# Pulgarcito_2.net
KiCad netlist of a schematic drawn in EasyEDA
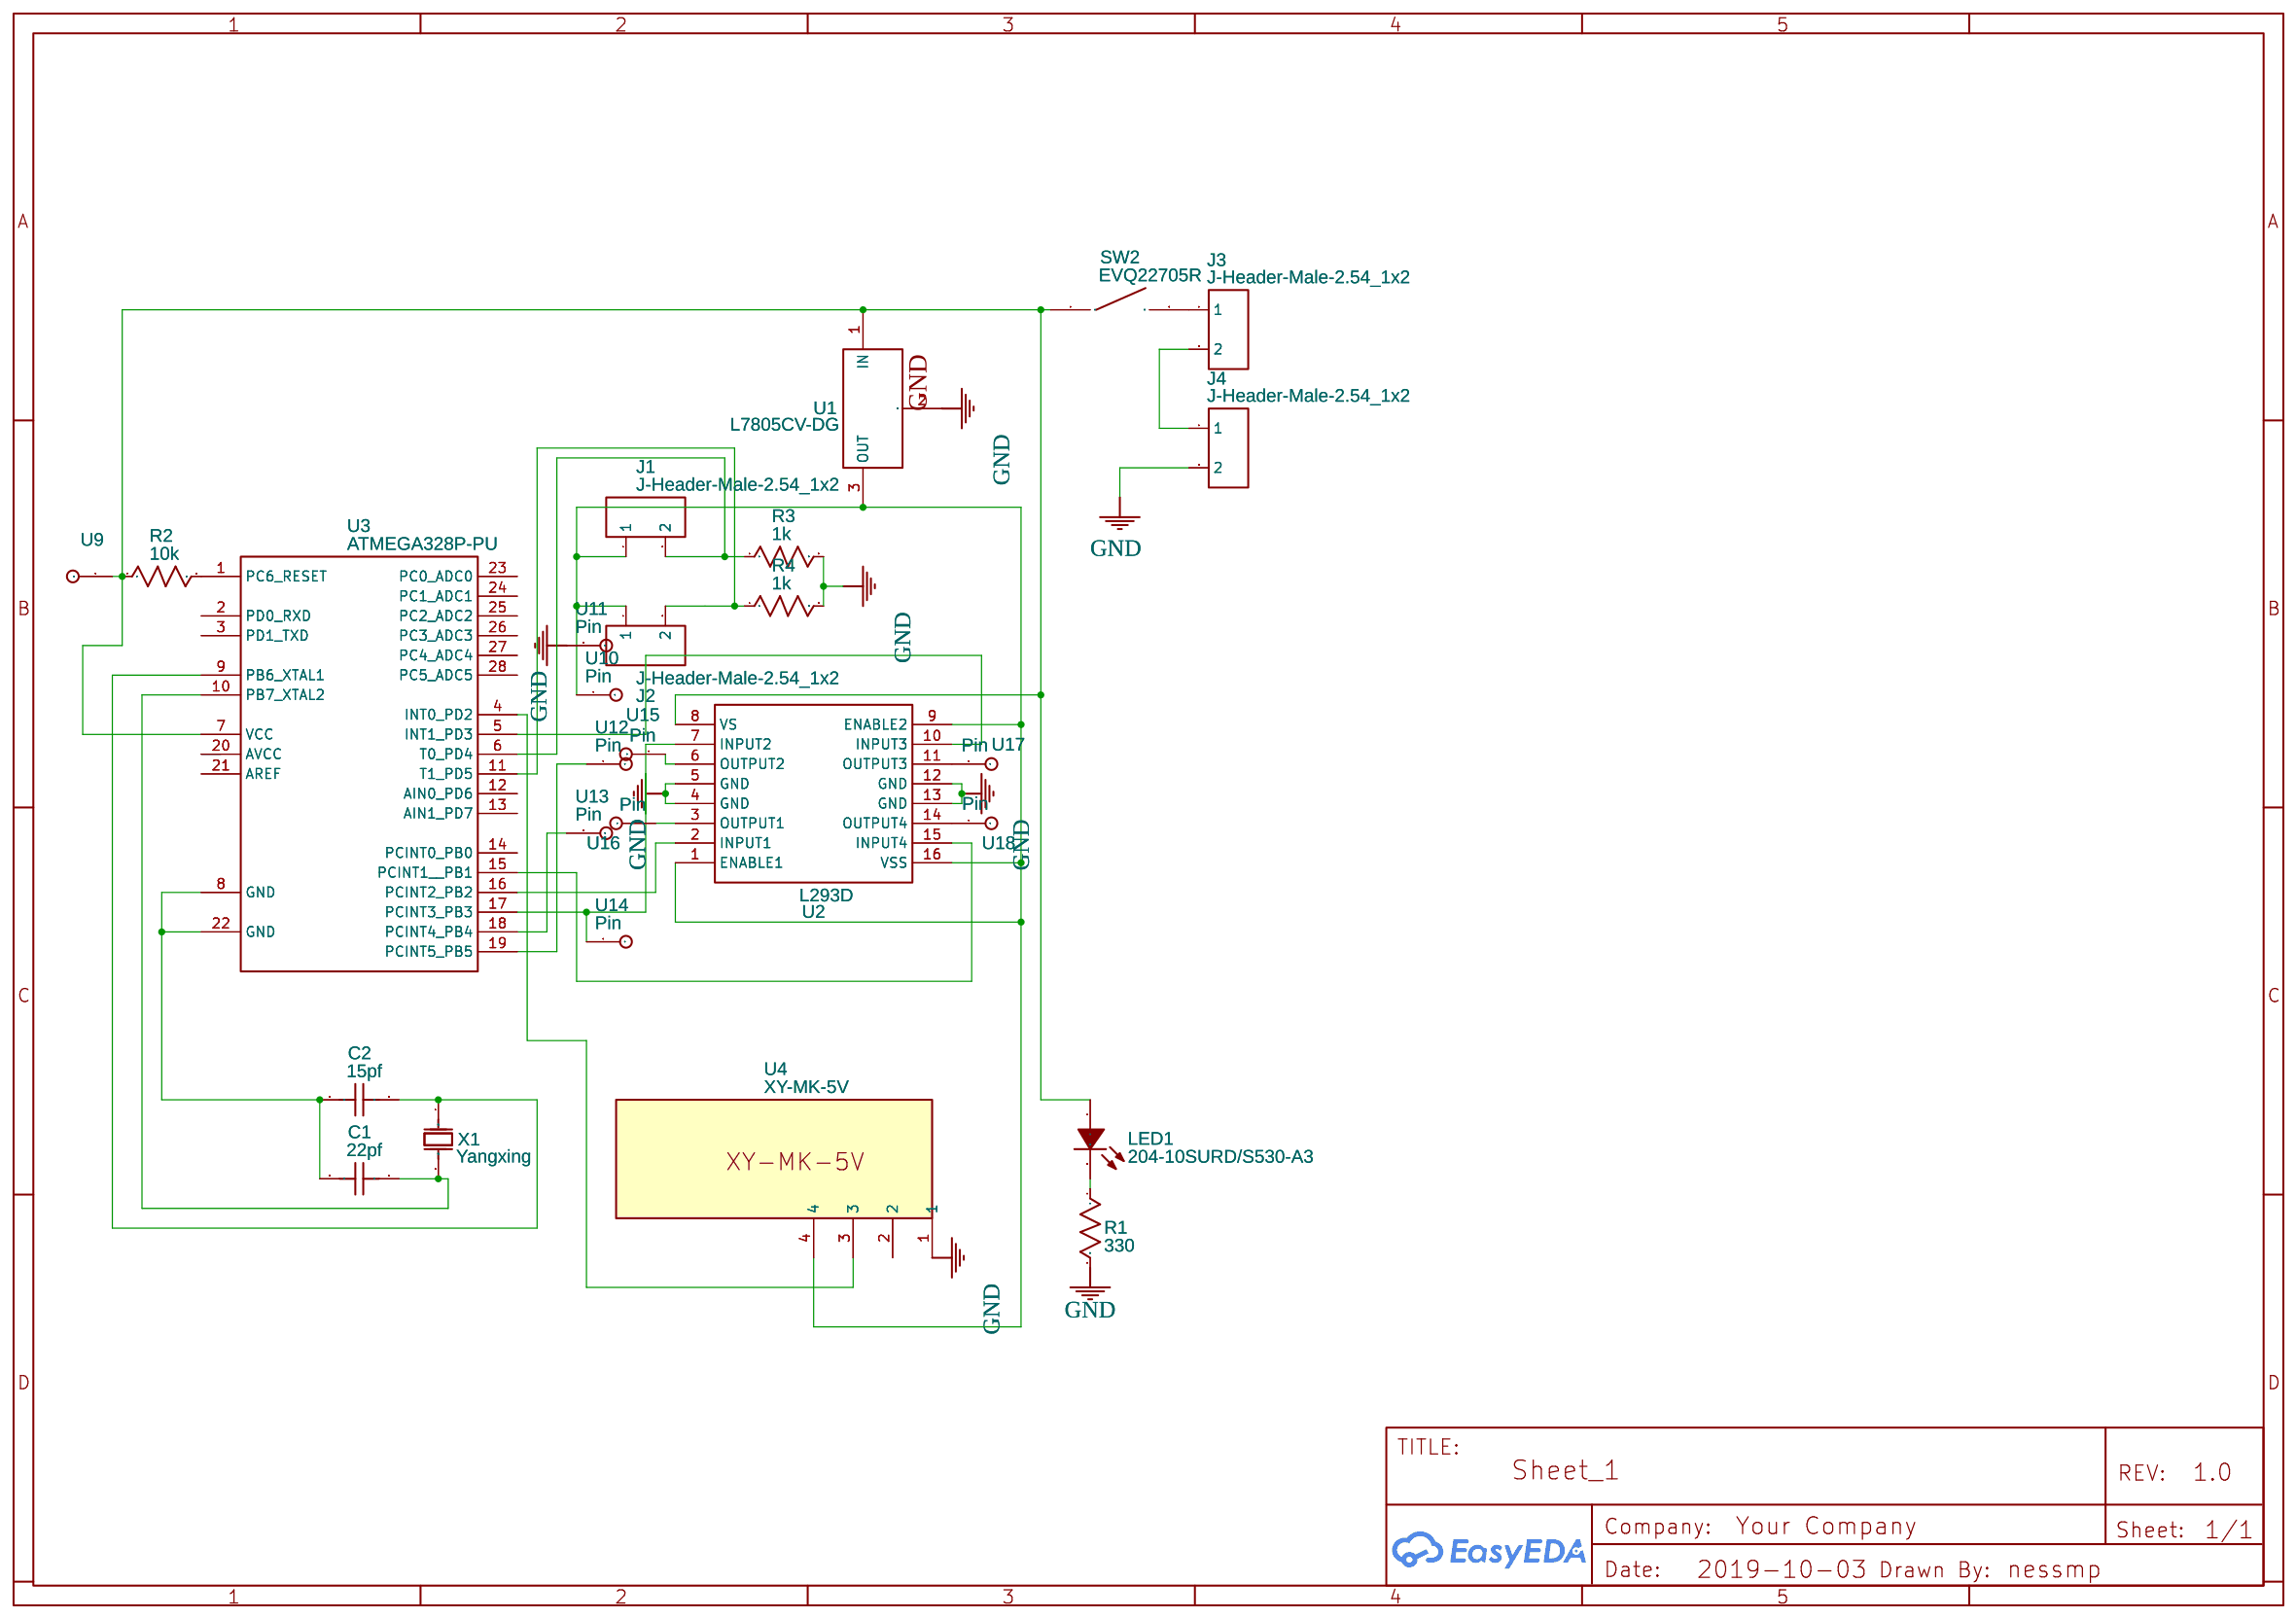
[diagram p0: schematic sheet]

(export (version "E")
  (design (tool "Eeschema 10.0.6"))
  (components
    (comp (ref "C1") (value "22pf") (libsource (lib "") (part "Cap_RAD-0.1_US")))
    (comp (ref "C2") (value "15pf") (libsource (lib "") (part "Cap_RAD-0.1_US")))
    (comp (ref "J1")
      (value "J-Header-Male-2.54_1x2")
      (fields (field (name "BOM_Manufacturer Part") "826629-2") (field (name "BOM_Supplier Part") "C86471"))
      (libsource (lib "") (part "Unknown_320_255"))
    )
    (comp (ref "J2")
      (value "J-Header-Male-2.54_1x2")
      (fields (field (name "BOM_Manufacturer Part") "826629-2") (field (name "BOM_Supplier Part") "C86471"))
      (libsource (lib "") (part "Unknown_320_320"))
    )
    (comp (ref "J3")
      (value "J-Header-Male-2.54_1x2")
      (fields (field (name "BOM_Manufacturer Part") "826629-2") (field (name "BOM_Supplier Part") "C86471"))
      (libsource (lib "") (part "Unknown_615_160"))
    )
    (comp (ref "J4")
      (value "J-Header-Male-2.54_1x2")
      (fields (field (name "BOM_Manufacturer Part") "826629-2") (field (name "BOM_Supplier Part") "C86471"))
      (libsource (lib "") (part "Unknown_615_220"))
    )
    (comp (ref "LED1")
      (value "204-10SURD/S530-A3")
      (fields (field (name "BOM_Supplier Part") "C99772"))
      (libsource (lib "") (part "Unknown_550_570"))
    )
    (comp (ref "R1") (value "330") (libsource (lib "") (part "Res_AXIAL-0.3(1/8W)_US")))
    (comp (ref "R2") (value "10k") (libsource (lib "") (part "Res_AXIAL-0.3(1/8W)_US_1")))
    (comp (ref "R3") (value "1k") (libsource (lib "") (part "Res_AXIAL-0.3(1/8W)_US_1")))
    (comp (ref "R4") (value "1k") (libsource (lib "") (part "Res_AXIAL-0.3(1/8W)_US_1")))
    (comp (ref "SW2")
      (value "EVQ22705R")
      (fields (field (name "BOM_Supplier Part") "C79156"))
      (libsource (lib "") (part "Unknown_560_150"))
    )
    (comp (ref "U1")
      (value "L7805CV-DG")
      (fields (field (name "BOM_Manufacturer Part") "L7806CV-DG") (field (name "BOM_Supplier Part") "C3796"))
      (libsource (lib "") (part "Unknown_445_200"))
    )
    (comp (ref "U2")
      (value "L293D")
      (fields (field (name "BOM_Supplier Part") "C12340"))
      (libsource (lib "") (part "Unknown_405_390"))
    )
    (comp (ref "U3")
      (value "ATMEGA328P-PU")
      (fields (field (name "BOM_Supplier Part") "C33901"))
      (libsource (lib "") (part "Unknown_175_380"))
    )
    (comp (ref "U4") (value "XY-MK-5V") (libsource (lib "") (part "Unknown_465_550")))
    (comp (ref "U9") (value "Pin") (libsource (lib "") (part "Unknown_30_285")))
    (comp (ref "U10") (value "Pin") (libsource (lib "") (part "Unknown_305_345")))
    (comp (ref "U11") (value "Pin") (libsource (lib "") (part "Unknown_300_320")))
    (comp (ref "U12") (value "Pin") (libsource (lib "") (part "Unknown_310_380")))
    (comp (ref "U13") (value "Pin") (libsource (lib "") (part "Unknown_300_415")))
    (comp (ref "U14") (value "Pin") (libsource (lib "") (part "Unknown_310_470")))
    (comp (ref "U15") (value "Pin") (libsource (lib "") (part "Unknown_310_375")))
    (comp (ref "U16") (value "Pin") (libsource (lib "") (part "Unknown_305_410")))
    (comp (ref "U17") (value "Pin") (libsource (lib "") (part "Unknown_495_380")))
    (comp (ref "U18") (value "Pin") (libsource (lib "") (part "Unknown_495_410")))
    (comp (ref "X1")
      (value "Yangxing")
      (fields (field (name "BOM_Supplier Part") "C12886"))
      (libsource (lib "") (part "25MHz 49S"))
    )
  )
  (nets
    (net (code "1") (name "GND") (class "Default")
      (node (ref "J4") (pin "2") (pinfunction "2_2") (pintype "unspecified"))
      (node (ref "R1") (pin "2") (pinfunction "2_2") (pintype "unspecified"))
      (node (ref "R3") (pin "2") (pinfunction "2_2") (pintype "unspecified"))
      (node (ref "R4") (pin "2") (pinfunction "2_2") (pintype "unspecified"))
      (node (ref "U1") (pin "2") (pinfunction "GND_2") (pintype "passive"))
      (node (ref "U11") (pin "1") (pinfunction "1_1") (pintype "unspecified"))
      (node (ref "U2") (pin "12") (pinfunction "GND_12") (pintype "unspecified"))
      (node (ref "U2") (pin "13") (pinfunction "GND_13") (pintype "unspecified"))
      (node (ref "U2") (pin "4") (pinfunction "GND_4") (pintype "unspecified"))
      (node (ref "U2") (pin "5") (pinfunction "GND_5") (pintype "unspecified"))
      (node (ref "U4") (pin "1") (pinfunction "1_1") (pintype "unspecified"))
    )
    (net (code "2") (name "Net-(C1-Pad2)") (class "Default")
      (node (ref "C1") (pin "2") (pinfunction "2_2") (pintype "unspecified"))
      (node (ref "C2") (pin "2") (pinfunction "2_2") (pintype "unspecified"))
      (node (ref "U3") (pin "22") (pinfunction "GND_22") (pintype "passive"))
      (node (ref "U3") (pin "8") (pinfunction "GND_8") (pintype "passive"))
    )
    (net (code "3") (name "Net-(J3-Pad1)") (class "Default")
      (node (ref "J3") (pin "1") (pinfunction "1_1") (pintype "unspecified"))
      (node (ref "SW2") (pin "2") (pinfunction "2_2") (pintype "input"))
    )
    (net (code "4") (name "Net-(J3-Pad2)") (class "Default")
      (node (ref "J3") (pin "2") (pinfunction "2_2") (pintype "unspecified"))
      (node (ref "J4") (pin "1") (pinfunction "1_1") (pintype "unspecified"))
    )
    (net (code "5") (name "Net-(LED1-A)") (class "Default")
      (node (ref "LED1") (pin "1") (pinfunction "A_1") (pintype "unspecified"))
      (node (ref "R2") (pin "1") (pinfunction "1_1") (pintype "unspecified"))
      (node (ref "SW2") (pin "1") (pinfunction "1_1") (pintype "input"))
      (node (ref "U1") (pin "1") (pinfunction "IN_1") (pintype "passive"))
      (node (ref "U2") (pin "8") (pinfunction "VS_8") (pintype "unspecified"))
      (node (ref "U3") (pin "7") (pinfunction "VCC_7") (pintype "passive"))
      (node (ref "U9") (pin "1") (pinfunction "1_1") (pintype "unspecified"))
    )
    (net (code "6") (name "Net-(LED1-K)") (class "Default")
      (node (ref "LED1") (pin "2") (pinfunction "K_2") (pintype "unspecified"))
      (node (ref "R1") (pin "1") (pinfunction "1_1") (pintype "unspecified"))
    )
    (net (code "7") (name "Net-(U1-OUT)") (class "Default")
      (node (ref "J1") (pin "1") (pinfunction "1_1") (pintype "unspecified"))
      (node (ref "J2") (pin "1") (pinfunction "1_1") (pintype "unspecified"))
      (node (ref "U1") (pin "3") (pinfunction "OUT_3") (pintype "passive"))
      (node (ref "U10") (pin "1") (pinfunction "1_1") (pintype "unspecified"))
      (node (ref "U2") (pin "1") (pinfunction "ENABLE1_1") (pintype "unspecified"))
      (node (ref "U2") (pin "16") (pinfunction "VSS_16") (pintype "unspecified"))
      (node (ref "U2") (pin "9") (pinfunction "ENABLE2_9") (pintype "unspecified"))
      (node (ref "U4") (pin "4") (pinfunction "4_4") (pintype "passive"))
    )
    (net (code "8") (name "Net-(U2-INPUT1)") (class "Default")
      (node (ref "U2") (pin "2") (pinfunction "INPUT1_2") (pintype "unspecified"))
      (node (ref "U3") (pin "16") (pinfunction "PCINT2_PB2_16") (pintype "bidirectional"))
    )
    (net (code "9") (name "Net-(U2-INPUT2)") (class "Default")
      (node (ref "U14") (pin "1") (pinfunction "1_1") (pintype "unspecified"))
      (node (ref "U2") (pin "7") (pinfunction "INPUT2_7") (pintype "unspecified"))
      (node (ref "U3") (pin "17") (pinfunction "PCINT3_PB3_17") (pintype "bidirectional"))
    )
    (net (code "10") (name "Net-(U2-INPUT3)") (class "Default")
      (node (ref "U2") (pin "10") (pinfunction "INPUT3_10") (pintype "unspecified"))
      (node (ref "U3") (pin "5") (pinfunction "INT1_PD3_5") (pintype "bidirectional"))
    )
    (net (code "11") (name "Net-(U2-INPUT4)") (class "Default")
      (node (ref "U2") (pin "15") (pinfunction "INPUT4_15") (pintype "unspecified"))
      (node (ref "U3") (pin "15") (pinfunction "PCINT1__PB1_15") (pintype "bidirectional"))
    )
    (net (code "12") (name "Net-(U2-OUTPUT1)") (class "Default")
      (node (ref "U16") (pin "1") (pinfunction "1_1") (pintype "unspecified"))
      (node (ref "U2") (pin "3") (pinfunction "OUTPUT1_3") (pintype "unspecified"))
    )
    (net (code "13") (name "Net-(U2-OUTPUT2)") (class "Default")
      (node (ref "U15") (pin "1") (pinfunction "1_1") (pintype "unspecified"))
      (node (ref "U2") (pin "6") (pinfunction "OUTPUT2_6") (pintype "unspecified"))
    )
    (net (code "14") (name "Net-(U2-OUTPUT3)") (class "Default")
      (node (ref "U17") (pin "1") (pinfunction "1_1") (pintype "unspecified"))
      (node (ref "U2") (pin "11") (pinfunction "OUTPUT3_11") (pintype "unspecified"))
    )
    (net (code "15") (name "Net-(U2-OUTPUT4)") (class "Default")
      (node (ref "U18") (pin "1") (pinfunction "1_1") (pintype "unspecified"))
      (node (ref "U2") (pin "14") (pinfunction "OUTPUT4_14") (pintype "unspecified"))
    )
    (net (code "16") (name "Net-(U3-INT0_PD2)") (class "Default")
      (node (ref "U3") (pin "4") (pinfunction "INT0_PD2_4") (pintype "bidirectional"))
      (node (ref "U4") (pin "3") (pinfunction "3_3") (pintype "input"))
    )
    (net (code "17") (name "Net-(U3-PB6_XTAL1)") (class "Default")
      (node (ref "C2") (pin "1") (pinfunction "1_1") (pintype "unspecified"))
      (node (ref "U3") (pin "9") (pinfunction "PB6_XTAL1_9") (pintype "bidirectional"))
      (node (ref "X1") (pin "1") (pinfunction "OSC1_1") (pintype "input"))
    )
    (net (code "18") (name "Net-(U3-PB7_XTAL2)") (class "Default")
      (node (ref "C1") (pin "1") (pinfunction "1_1") (pintype "unspecified"))
      (node (ref "U3") (pin "10") (pinfunction "PB7_XTAL2_10") (pintype "bidirectional"))
      (node (ref "X1") (pin "2") (pinfunction "OSC2_2") (pintype "input"))
    )
    (net (code "19") (name "Net-(U3-PC6_RESET)") (class "Default")
      (node (ref "R2") (pin "2") (pinfunction "2_2") (pintype "unspecified"))
      (node (ref "U3") (pin "1") (pinfunction "PC6_RESET_1") (pintype "bidirectional"))
    )
    (net (code "20") (name "Net-(U3-PCINT4_PB4)") (class "Default")
      (node (ref "U13") (pin "1") (pinfunction "1_1") (pintype "unspecified"))
      (node (ref "U3") (pin "18") (pinfunction "PCINT4_PB4_18") (pintype "bidirectional"))
    )
    (net (code "21") (name "Net-(U3-PCINT5_PB5)") (class "Default")
      (node (ref "U12") (pin "1") (pinfunction "1_1") (pintype "unspecified"))
      (node (ref "U3") (pin "19") (pinfunction "PCINT5_PB5_19") (pintype "bidirectional"))
    )
    (net (code "22") (name "Net-(U3-T0_PD4)") (class "Default")
      (node (ref "J1") (pin "2") (pinfunction "2_2") (pintype "unspecified"))
      (node (ref "R3") (pin "1") (pinfunction "1_1") (pintype "unspecified"))
      (node (ref "U3") (pin "6") (pinfunction "T0_PD4_6") (pintype "bidirectional"))
    )
    (net (code "23") (name "Net-(U3-T1_PD5)") (class "Default")
      (node (ref "J2") (pin "2") (pinfunction "2_2") (pintype "unspecified"))
      (node (ref "R4") (pin "1") (pinfunction "1_1") (pintype "unspecified"))
      (node (ref "U3") (pin "11") (pinfunction "T1_PD5_11") (pintype "bidirectional"))
    )
    (net (code "24") (name "unconnected-(U3-AIN0_PD6-Pad12)") (class "Default")
      (node (ref "U3") (pin "12") (pinfunction "AIN0_PD6_12") (pintype "bidirectional"))
    )
    (net (code "25") (name "unconnected-(U3-AIN1_PD7-Pad13)") (class "Default")
      (node (ref "U3") (pin "13") (pinfunction "AIN1_PD7_13") (pintype "bidirectional"))
    )
    (net (code "26") (name "unconnected-(U3-AREF-Pad21)") (class "Default")
      (node (ref "U3") (pin "21") (pinfunction "AREF_21") (pintype "passive"))
    )
    (net (code "27") (name "unconnected-(U3-AVCC-Pad20)") (class "Default")
      (node (ref "U3") (pin "20") (pinfunction "AVCC_20") (pintype "passive"))
    )
    (net (code "28") (name "unconnected-(U3-PC0_ADC0-Pad23)") (class "Default")
      (node (ref "U3") (pin "23") (pinfunction "PC0_ADC0_23") (pintype "bidirectional"))
    )
    (net (code "29") (name "unconnected-(U3-PC1_ADC1-Pad24)") (class "Default")
      (node (ref "U3") (pin "24") (pinfunction "PC1_ADC1_24") (pintype "bidirectional"))
    )
    (net (code "30") (name "unconnected-(U3-PC2_ADC2-Pad25)") (class "Default")
      (node (ref "U3") (pin "25") (pinfunction "PC2_ADC2_25") (pintype "bidirectional"))
    )
    (net (code "31") (name "unconnected-(U3-PC3_ADC3-Pad26)") (class "Default")
      (node (ref "U3") (pin "26") (pinfunction "PC3_ADC3_26") (pintype "bidirectional"))
    )
    (net (code "32") (name "unconnected-(U3-PC4_ADC4-Pad27)") (class "Default")
      (node (ref "U3") (pin "27") (pinfunction "PC4_ADC4_27") (pintype "bidirectional"))
    )
    (net (code "33") (name "unconnected-(U3-PC5_ADC5-Pad28)") (class "Default")
      (node (ref "U3") (pin "28") (pinfunction "PC5_ADC5_28") (pintype "bidirectional"))
    )
    (net (code "34") (name "unconnected-(U3-PCINT0_PB0-Pad14)") (class "Default")
      (node (ref "U3") (pin "14") (pinfunction "PCINT0_PB0_14") (pintype "bidirectional"))
    )
    (net (code "35") (name "unconnected-(U3-PD0_RXD-Pad2)") (class "Default")
      (node (ref "U3") (pin "2") (pinfunction "PD0_RXD_2") (pintype "bidirectional"))
    )
    (net (code "36") (name "unconnected-(U3-PD1_TXD-Pad3)") (class "Default")
      (node (ref "U3") (pin "3") (pinfunction "PD1_TXD_3") (pintype "bidirectional"))
    )
    (net (code "37") (name "unconnected-(U4-Pad2)") (class "Default")
      (node (ref "U4") (pin "2") (pinfunction "2_2") (pintype "passive"))
    )
  )
)
